# 06_POWER_MEASUREMENT.net
KiCad netlist of a schematic drawn in Altium Designer
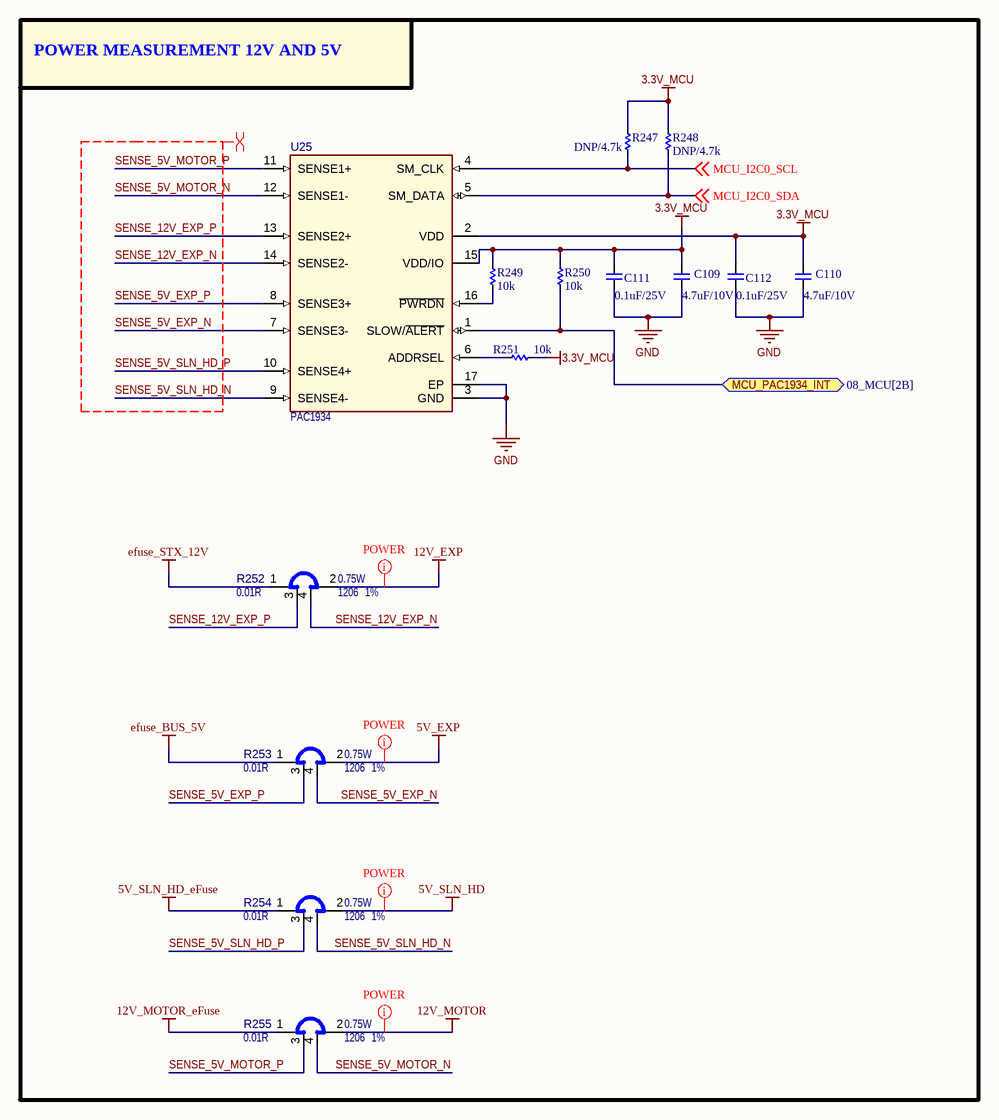
[diagram p0: 06_POWER_MEASUREMENT.SchDoc]

(export (version "E")
  (design (tool "Eeschema 10.0.6"))
  (components
    (comp (ref "C109")
      (value "4.7uF/10V")
      (footprint "CAP_C_1005X60")
      (description "CAP")
      (libsource (lib "LABLIB") (part "_CAP_C_2"))
    )
    (comp (ref "C110")
      (value "4.7uF/10V")
      (footprint "CAP_C_1005X60")
      (description "CAP")
      (libsource (lib "LABLIB") (part "_CAP_C_2"))
    )
    (comp (ref "C111")
      (value "0.1uF/25V")
      (footprint "CAP_C_1005X60")
      (description "CAP")
      (libsource (lib "LABLIB") (part "_CAP_C_2"))
    )
    (comp (ref "C112")
      (value "0.1uF/25V")
      (footprint "CAP_C_1005X60")
      (description "CAP")
      (libsource (lib "LABLIB") (part "_CAP_C_2"))
    )
    (comp (ref "R247")
      (value "DNP/4.7k")
      (footprint "RES_C_1005X40")
      (description "RES")
      (libsource (lib "LABLIB") (part "_RES_B_2"))
    )
    (comp (ref "R248")
      (value "DNP/4.7k")
      (footprint "RES_C_1005X40")
      (description "RES")
      (libsource (lib "LABLIB") (part "_RES_B_2"))
    )
    (comp (ref "R249")
      (value "10k")
      (footprint "RES_C_1005X40")
      (description "RES")
      (libsource (lib "LABLIB") (part "_RES_B_2"))
    )
    (comp (ref "R250")
      (value "10k")
      (footprint "RES_C_1005X40")
      (description "RES")
      (libsource (lib "LABLIB") (part "_RES_B_2"))
    )
    (comp (ref "R251")
      (value "10k")
      (footprint "RES_C_1005X40")
      (description "RES")
      (libsource (lib "LABLIB") (part "_RES_B_2"))
    )
    (comp (ref "R252")
      (value "0.01R")
      (footprint "RES_C_1206_SHUNT")
      (description "Shunt")
      (fields
        (field (name "PACKAGE") "1206")
        (field (name "TOLERANCE") "1%")
        (field (name "POWER") "0.75W")
        (field (name "Comment") "KRL1632E-M-R010-F-T5")
        (field (name "OWNER") "Ciprian Abramov")
      )
      (libsource (lib "LABLIB") (part "Shunt 4 Pin"))
    )
    (comp (ref "R253")
      (value "0.01R")
      (footprint "RES_C_1206_SHUNT")
      (description "Shunt")
      (fields
        (field (name "PACKAGE") "1206")
        (field (name "TOLERANCE") "1%")
        (field (name "POWER") "0.75W")
        (field (name "Comment") "KRL1632E-M-R010-F-T5")
        (field (name "OWNER") "Ciprian Abramov")
      )
      (libsource (lib "LABLIB") (part "Shunt 4 Pin"))
    )
    (comp (ref "R254")
      (value "0.01R")
      (footprint "RES_C_1206_SHUNT")
      (description "Shunt")
      (fields
        (field (name "PACKAGE") "1206")
        (field (name "TOLERANCE") "1%")
        (field (name "POWER") "0.75W")
        (field (name "Comment") "KRL1632E-M-R010-F-T5")
        (field (name "OWNER") "Ciprian Abramov")
      )
      (libsource (lib "LABLIB") (part "Shunt 4 Pin"))
    )
    (comp (ref "R255")
      (value "0.01R")
      (footprint "RES_C_1206_SHUNT")
      (description "Shunt")
      (fields
        (field (name "PACKAGE") "1206")
        (field (name "TOLERANCE") "1%")
        (field (name "POWER") "0.75W")
        (field (name "Comment") "KRL1632E-M-R010-F-T5")
        (field (name "OWNER") "Ciprian Abramov")
      )
      (libsource (lib "LABLIB") (part "Shunt 4 Pin"))
    )
    (comp (ref "U25")
      (value "PAC1934")
      (footprint "UQFN-16_4X4_EP2.6X2.6")
      (fields (field (name "Comment") "PAC1934 UQFN-16") (field (name "OWNER") "Ciprian Abramov"))
      (libsource (lib "LABLIB") (part "PAC1934 UQFN-16"))
    )
  )
  (nets
    (net (code "1") (name "/MCU_PAC1934_INT") (class "Default")
      (node (ref "R250") (pin "2") (pinfunction "2_2") (pintype "passive"))
      (node (ref "U25") (pin "1") (pinfunction "SLOW/~{ALERT}_1") (pintype "bidirectional"))
    )
    (net (code "2") (name "/SENSE_5V_EXP_N") (class "Default")
      (node (ref "R253") (pin "4") (pinfunction "4_4") (pintype "passive"))
      (node (ref "U25") (pin "7") (pinfunction "SENSE3-_7") (pintype "input"))
    )
    (net (code "3") (name "/SENSE_5V_EXP_P") (class "Default")
      (node (ref "R253") (pin "3") (pinfunction "3_3") (pintype "passive"))
      (node (ref "U25") (pin "8") (pinfunction "SENSE3+_8") (pintype "input"))
    )
    (net (code "4") (name "/SENSE_5V_MOTOR_N") (class "Default")
      (node (ref "R255") (pin "4") (pinfunction "4_4") (pintype "passive"))
      (node (ref "U25") (pin "12") (pinfunction "SENSE1-_12") (pintype "input"))
    )
    (net (code "5") (name "/SENSE_5V_MOTOR_P") (class "Default")
      (node (ref "R255") (pin "3") (pinfunction "3_3") (pintype "passive"))
      (node (ref "U25") (pin "11") (pinfunction "SENSE1+_11") (pintype "input"))
    )
    (net (code "6") (name "/SENSE_5V_SLN_HD_N") (class "Default")
      (node (ref "R254") (pin "4") (pinfunction "4_4") (pintype "passive"))
      (node (ref "U25") (pin "9") (pinfunction "SENSE4-_9") (pintype "input"))
    )
    (net (code "7") (name "/SENSE_5V_SLN_HD_P") (class "Default")
      (node (ref "R254") (pin "3") (pinfunction "3_3") (pintype "passive"))
      (node (ref "U25") (pin "10") (pinfunction "SENSE4+_10") (pintype "input"))
    )
    (net (code "8") (name "/SENSE_12V_EXP_N") (class "Default")
      (node (ref "R252") (pin "4") (pinfunction "4_4") (pintype "passive"))
      (node (ref "U25") (pin "14") (pinfunction "SENSE2-_14") (pintype "input"))
    )
    (net (code "9") (name "/SENSE_12V_EXP_P") (class "Default")
      (node (ref "R252") (pin "3") (pinfunction "3_3") (pintype "passive"))
      (node (ref "U25") (pin "13") (pinfunction "SENSE2+_13") (pintype "input"))
    )
    (net (code "10") (name "3.3V_MCU") (class "Default")
      (node (ref "C109") (pin "1") (pinfunction "1_1") (pintype "passive"))
      (node (ref "C110") (pin "1") (pinfunction "1_1") (pintype "passive"))
      (node (ref "C111") (pin "1") (pinfunction "1_1") (pintype "passive"))
      (node (ref "C112") (pin "1") (pinfunction "1_1") (pintype "passive"))
      (node (ref "R247") (pin "1") (pinfunction "1_1") (pintype "passive"))
      (node (ref "R248") (pin "1") (pinfunction "1_1") (pintype "passive"))
      (node (ref "R249") (pin "1") (pinfunction "1_1") (pintype "passive"))
      (node (ref "R250") (pin "1") (pinfunction "1_1") (pintype "passive"))
      (node (ref "R251") (pin "2") (pinfunction "2_2") (pintype "passive"))
      (node (ref "U25") (pin "15") (pinfunction "VDD/IO_15") (pintype "power_in"))
      (node (ref "U25") (pin "2") (pinfunction "VDD_2") (pintype "power_in"))
    )
    (net (code "11") (name "5V_EXP") (class "Default")
      (node (ref "R253") (pin "2") (pinfunction "2_2") (pintype "passive"))
    )
    (net (code "12") (name "5V_SLN_HD") (class "Default")
      (node (ref "R254") (pin "2") (pinfunction "2_2") (pintype "passive"))
    )
    (net (code "13") (name "5V_SLN_HD_eFuse") (class "Default")
      (node (ref "R254") (pin "1") (pinfunction "1_1") (pintype "passive"))
    )
    (net (code "14") (name "12V_EXP") (class "Default")
      (node (ref "R252") (pin "2") (pinfunction "2_2") (pintype "passive"))
    )
    (net (code "15") (name "12V_MOTOR") (class "Default")
      (node (ref "R255") (pin "2") (pinfunction "2_2") (pintype "passive"))
    )
    (net (code "16") (name "12V_MOTOR_eFuse") (class "Default")
      (node (ref "R255") (pin "1") (pinfunction "1_1") (pintype "passive"))
    )
    (net (code "17") (name "GND") (class "Default")
      (node (ref "C109") (pin "2") (pinfunction "2_2") (pintype "passive"))
      (node (ref "C110") (pin "2") (pinfunction "2_2") (pintype "passive"))
      (node (ref "C111") (pin "2") (pinfunction "2_2") (pintype "passive"))
      (node (ref "C112") (pin "2") (pinfunction "2_2") (pintype "passive"))
      (node (ref "U25") (pin "17") (pinfunction "EP_17") (pintype "passive"))
      (node (ref "U25") (pin "3") (pinfunction "GND_3") (pintype "power_in"))
    )
    (net (code "18") (name "MCU_I2C0_SCL") (class "Default")
      (node (ref "R247") (pin "2") (pinfunction "2_2") (pintype "passive"))
      (node (ref "U25") (pin "4") (pinfunction "SM_CLK_4") (pintype "input"))
    )
    (net (code "19") (name "MCU_I2C0_SDA") (class "Default")
      (node (ref "R248") (pin "2") (pinfunction "2_2") (pintype "passive"))
      (node (ref "U25") (pin "5") (pinfunction "SM_DATA_5") (pintype "bidirectional"))
    )
    (net (code "20") (name "Net-(U25-ADDRSEL)") (class "Default")
      (node (ref "R251") (pin "1") (pinfunction "1_1") (pintype "passive"))
      (node (ref "U25") (pin "6") (pinfunction "ADDRSEL_6") (pintype "input"))
    )
    (net (code "21") (name "Net-(U25-~{PWRDN})") (class "Default")
      (node (ref "R249") (pin "2") (pinfunction "2_2") (pintype "passive"))
      (node (ref "U25") (pin "16") (pinfunction "~{PWRDN}_16") (pintype "input"))
    )
    (net (code "22") (name "efuse_BUS_5V") (class "Default")
      (node (ref "R253") (pin "1") (pinfunction "1_1") (pintype "passive"))
    )
    (net (code "23") (name "efuse_STX_12V") (class "Default")
      (node (ref "R252") (pin "1") (pinfunction "1_1") (pintype "passive"))
    )
  )
)
